# teclado_at_f340_smd_v2.net
KiCad netlist of a schematic drawn in EAGLE
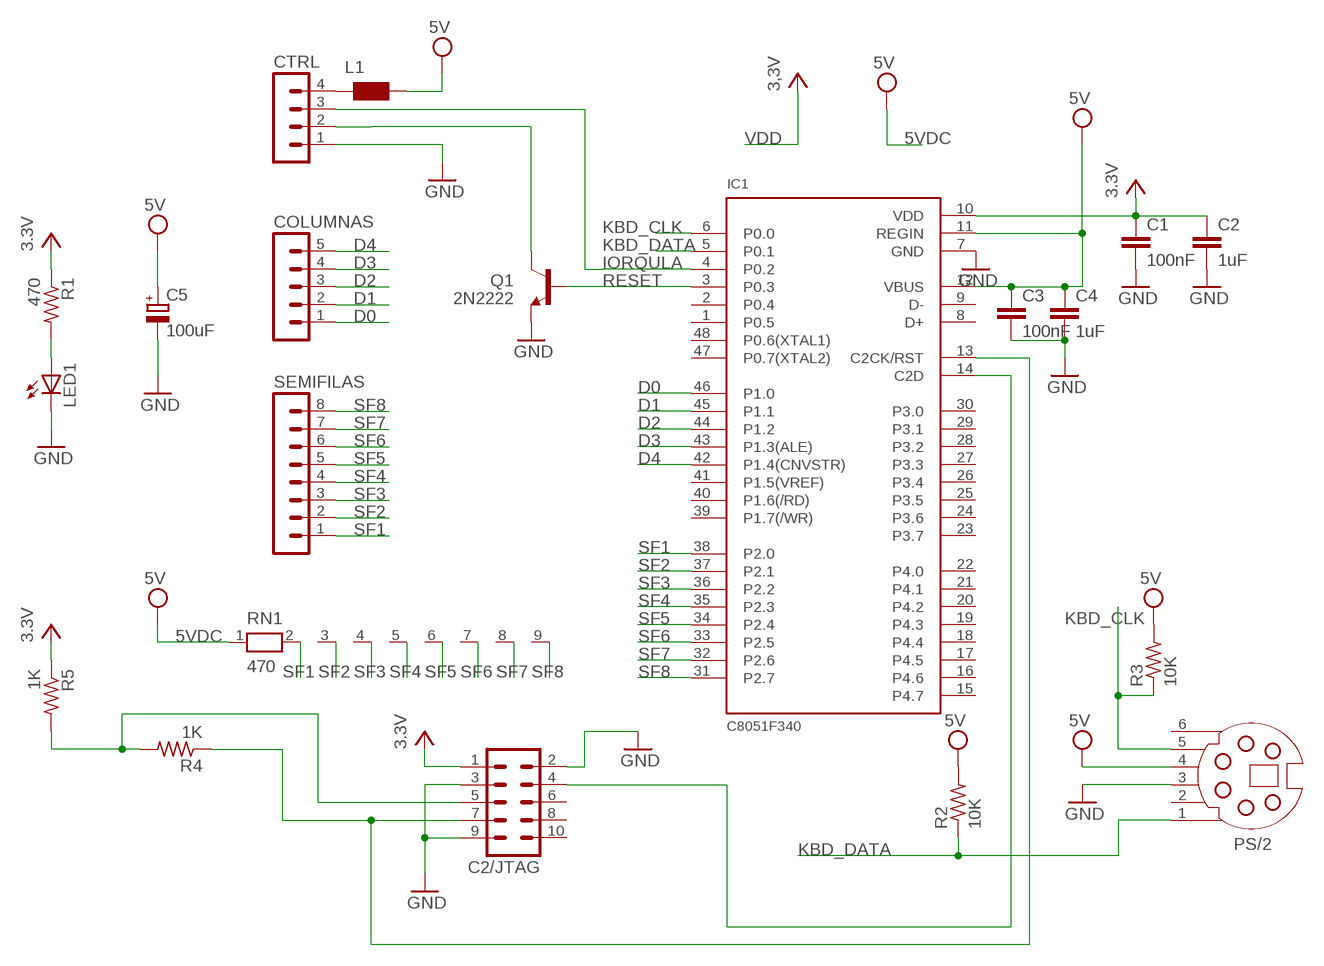
[diagram p0: schematic, sheet 1]

(export (version "E")
  (design (tool "Eeschema 10.0.6"))
  (components
    (comp (ref "C1")
      (value "100nF")
      (footprint "eagle-import:C0805K")
      (libsource (lib "eagle-import") (part "C-EUC0805K"))
    )
    (comp (ref "C2")
      (value "1uF")
      (footprint "eagle-import:C0805K")
      (libsource (lib "eagle-import") (part "C-EUC0805K"))
    )
    (comp (ref "C2/JTAG")
      (value "MA05-2")
      (footprint "eagle-import:MA05-2")
      (libsource (lib "eagle-import") (part "MA05-2"))
    )
    (comp (ref "C3")
      (value "100nF")
      (footprint "eagle-import:C0805K")
      (libsource (lib "eagle-import") (part "C-EUC0805K"))
    )
    (comp (ref "C4")
      (value "1uF")
      (footprint "eagle-import:C0805K")
      (libsource (lib "eagle-import") (part "C-EUC0805K"))
    )
    (comp (ref "C5")
      (value "100uF")
      (footprint "eagle-import:E2,5-6E")
      (libsource (lib "eagle-import") (part "CPOL-EUE2,5-6E"))
    )
    (comp (ref "COLUMNAS")
      (value "MA05-1")
      (footprint "eagle-import:MA05-1")
      (libsource (lib "eagle-import") (part "MA05-1"))
    )
    (comp (ref "CTRL")
      (value "MA04-1")
      (footprint "eagle-import:MA04-1")
      (libsource (lib "eagle-import") (part "MA04-1"))
    )
    (comp (ref "IC1")
      (value "C8051F340")
      (footprint "eagle-import:TQFP48")
      (libsource (lib "eagle-import") (part "C8051F340"))
    )
    (comp (ref "L1")
      (value "WE-CBF_0805")
      (footprint "eagle-import:0805")
      (libsource (lib "eagle-import") (part "WE-CBF_0805"))
    )
    (comp (ref "LED1")
      (value "LEDCHIP-LED0805")
      (footprint "eagle-import:CHIP-LED0805")
      (libsource (lib "eagle-import") (part "LEDCHIP-LED0805"))
    )
    (comp (ref "PS/2")
      (value "SSV-G06")
      (footprint "eagle-import:SSV-BC06")
      (libsource (lib "eagle-import") (part "SSV-G06"))
    )
    (comp (ref "Q1")
      (value "2N2222")
      (footprint "eagle-import:SOT23-3")
      (libsource (lib "eagle-import") (part "TRANSISTOR_NPNSOT23-3"))
    )
    (comp (ref "R1")
      (value "470")
      (footprint "eagle-import:M0805")
      (libsource (lib "eagle-import") (part "R-US_M0805"))
    )
    (comp (ref "R2")
      (value "10K")
      (footprint "eagle-import:M0805")
      (libsource (lib "eagle-import") (part "R-US_M0805"))
    )
    (comp (ref "R3")
      (value "10K")
      (footprint "eagle-import:M0805")
      (libsource (lib "eagle-import") (part "R-US_M0805"))
    )
    (comp (ref "R4")
      (value "1K")
      (footprint "eagle-import:M0805")
      (libsource (lib "eagle-import") (part "R-US_M0805"))
    )
    (comp (ref "R5")
      (value "1K")
      (footprint "eagle-import:M0805")
      (libsource (lib "eagle-import") (part "R-US_M0805"))
    )
    (comp (ref "RN1")
      (value "470")
      (footprint "eagle-import:RN-9")
      (libsource (lib "eagle-import") (part "RN08"))
    )
    (comp (ref "SEMIFILAS")
      (value "MA08-1")
      (footprint "eagle-import:MA08-1")
      (libsource (lib "eagle-import") (part "MA08-1"))
    )
  )
  (nets
    (net (code "1") (name "/D0") (class "Default")
      (node (ref "COLUMNAS") (pin "1") (pinfunction "1_1") (pintype "passive"))
      (node (ref "IC1") (pin "46") (pinfunction "P1.0_46") (pintype "bidirectional"))
    )
    (net (code "2") (name "/D1") (class "Default")
      (node (ref "COLUMNAS") (pin "2") (pinfunction "2_2") (pintype "passive"))
      (node (ref "IC1") (pin "45") (pinfunction "P1.1_45") (pintype "bidirectional"))
    )
    (net (code "3") (name "/D2") (class "Default")
      (node (ref "COLUMNAS") (pin "3") (pinfunction "3_3") (pintype "passive"))
      (node (ref "IC1") (pin "44") (pinfunction "P1.2_44") (pintype "bidirectional"))
    )
    (net (code "4") (name "/D3") (class "Default")
      (node (ref "COLUMNAS") (pin "4") (pinfunction "4_4") (pintype "passive"))
      (node (ref "IC1") (pin "43") (pinfunction "P1.3(ALE)_43") (pintype "bidirectional"))
    )
    (net (code "5") (name "/D4") (class "Default")
      (node (ref "COLUMNAS") (pin "5") (pinfunction "5_5") (pintype "passive"))
      (node (ref "IC1") (pin "42") (pinfunction "P1.4(CNVSTR)_42") (pintype "bidirectional"))
    )
    (net (code "6") (name "/IORQULA") (class "Default")
      (node (ref "CTRL") (pin "3") (pinfunction "3_3") (pintype "passive"))
      (node (ref "IC1") (pin "4") (pinfunction "P0.2_4") (pintype "bidirectional"))
    )
    (net (code "7") (name "/KBD_CLK") (class "Default")
      (node (ref "IC1") (pin "6") (pinfunction "P0.0_6") (pintype "bidirectional"))
      (node (ref "PS/2") (pin "5") (pinfunction "5_5") (pintype "passive"))
      (node (ref "R3") (pin "1") (pinfunction "1_1") (pintype "passive"))
    )
    (net (code "8") (name "/KBD_DATA") (class "Default")
      (node (ref "IC1") (pin "5") (pinfunction "P0.1_5") (pintype "bidirectional"))
      (node (ref "PS/2") (pin "1") (pinfunction "1_1") (pintype "passive"))
      (node (ref "R2") (pin "1") (pinfunction "1_1") (pintype "passive"))
    )
    (net (code "9") (name "/RESET") (class "Default")
      (node (ref "IC1") (pin "3") (pinfunction "P0.3_3") (pintype "bidirectional"))
      (node (ref "Q1") (pin "1") (pinfunction "B_1") (pintype "passive"))
    )
    (net (code "10") (name "/SF1") (class "Default")
      (node (ref "IC1") (pin "38") (pinfunction "P2.0_38") (pintype "bidirectional"))
      (node (ref "RN1") (pin "2") (pinfunction "2_2") (pintype "passive"))
      (node (ref "SEMIFILAS") (pin "1") (pinfunction "1_1") (pintype "passive"))
    )
    (net (code "11") (name "/SF2") (class "Default")
      (node (ref "IC1") (pin "37") (pinfunction "P2.1_37") (pintype "bidirectional"))
      (node (ref "RN1") (pin "3") (pinfunction "3_3") (pintype "passive"))
      (node (ref "SEMIFILAS") (pin "2") (pinfunction "2_2") (pintype "passive"))
    )
    (net (code "12") (name "/SF3") (class "Default")
      (node (ref "IC1") (pin "36") (pinfunction "P2.2_36") (pintype "bidirectional"))
      (node (ref "RN1") (pin "4") (pinfunction "4_4") (pintype "passive"))
      (node (ref "SEMIFILAS") (pin "3") (pinfunction "3_3") (pintype "passive"))
    )
    (net (code "13") (name "/SF4") (class "Default")
      (node (ref "IC1") (pin "35") (pinfunction "P2.3_35") (pintype "bidirectional"))
      (node (ref "RN1") (pin "5") (pinfunction "5_5") (pintype "passive"))
      (node (ref "SEMIFILAS") (pin "4") (pinfunction "4_4") (pintype "passive"))
    )
    (net (code "14") (name "/SF5") (class "Default")
      (node (ref "IC1") (pin "34") (pinfunction "P2.4_34") (pintype "bidirectional"))
      (node (ref "RN1") (pin "6") (pinfunction "6_6") (pintype "passive"))
      (node (ref "SEMIFILAS") (pin "5") (pinfunction "5_5") (pintype "passive"))
    )
    (net (code "15") (name "/SF6") (class "Default")
      (node (ref "IC1") (pin "33") (pinfunction "P2.5_33") (pintype "bidirectional"))
      (node (ref "RN1") (pin "7") (pinfunction "7_7") (pintype "passive"))
      (node (ref "SEMIFILAS") (pin "6") (pinfunction "6_6") (pintype "passive"))
    )
    (net (code "16") (name "/SF7") (class "Default")
      (node (ref "IC1") (pin "32") (pinfunction "P2.6_32") (pintype "bidirectional"))
      (node (ref "RN1") (pin "8") (pinfunction "8_8") (pintype "passive"))
      (node (ref "SEMIFILAS") (pin "7") (pinfunction "7_7") (pintype "passive"))
    )
    (net (code "17") (name "/SF8") (class "Default")
      (node (ref "IC1") (pin "31") (pinfunction "P2.7_31") (pintype "bidirectional"))
      (node (ref "RN1") (pin "9") (pinfunction "9_9") (pintype "passive"))
      (node (ref "SEMIFILAS") (pin "8") (pinfunction "8_8") (pintype "passive"))
    )
    (net (code "18") (name "3,3V") (class "Default")
      (node (ref "C1") (pin "1") (pinfunction "1_1") (pintype "passive"))
      (node (ref "C2") (pin "1") (pinfunction "1_1") (pintype "passive"))
      (node (ref "C2/JTAG") (pin "1") (pinfunction "1_1") (pintype "passive"))
      (node (ref "IC1") (pin "10") (pinfunction "VDD_10") (pintype "power_in"))
      (node (ref "R1") (pin "1") (pinfunction "1_1") (pintype "passive"))
      (node (ref "R5") (pin "1") (pinfunction "1_1") (pintype "passive"))
    )
    (net (code "19") (name "5V") (class "Default")
      (node (ref "C3") (pin "1") (pinfunction "1_1") (pintype "passive"))
      (node (ref "C4") (pin "1") (pinfunction "1_1") (pintype "passive"))
      (node (ref "C5") (pin "+") (pinfunction "+_+") (pintype "passive"))
      (node (ref "IC1") (pin "11") (pinfunction "REGIN_11") (pintype "power_in"))
      (node (ref "IC1") (pin "12") (pinfunction "VBUS_12") (pintype "power_in"))
      (node (ref "L1") (pin "2") (pinfunction "2_2") (pintype "passive"))
      (node (ref "PS/2") (pin "4") (pinfunction "4_4") (pintype "passive"))
      (node (ref "R2") (pin "2") (pinfunction "2_2") (pintype "passive"))
      (node (ref "R3") (pin "2") (pinfunction "2_2") (pintype "passive"))
      (node (ref "RN1") (pin "1") (pinfunction "1_1") (pintype "passive"))
    )
    (net (code "20") (name "GND") (class "Default")
      (node (ref "C1") (pin "2") (pinfunction "2_2") (pintype "passive"))
      (node (ref "C2") (pin "2") (pinfunction "2_2") (pintype "passive"))
      (node (ref "C2/JTAG") (pin "2") (pinfunction "2_2") (pintype "passive"))
      (node (ref "C2/JTAG") (pin "3") (pinfunction "3_3") (pintype "passive"))
      (node (ref "C2/JTAG") (pin "9") (pinfunction "9_9") (pintype "passive"))
      (node (ref "C3") (pin "2") (pinfunction "2_2") (pintype "passive"))
      (node (ref "C4") (pin "2") (pinfunction "2_2") (pintype "passive"))
      (node (ref "C5") (pin "-") (pinfunction "-_-") (pintype "passive"))
      (node (ref "CTRL") (pin "1") (pinfunction "1_1") (pintype "passive"))
      (node (ref "IC1") (pin "7") (pinfunction "GND_7") (pintype "power_in"))
      (node (ref "LED1") (pin "C") (pinfunction "C_C") (pintype "passive"))
      (node (ref "PS/2") (pin "3") (pinfunction "3_3") (pintype "passive"))
      (node (ref "Q1") (pin "2") (pinfunction "E_2") (pintype "passive"))
    )
    (net (code "21") (name "Net-(C2/JTAG-Pad5)") (class "Default")
      (node (ref "C2/JTAG") (pin "5") (pinfunction "5_5") (pintype "passive"))
      (node (ref "R4") (pin "2") (pinfunction "2_2") (pintype "passive"))
      (node (ref "R5") (pin "2") (pinfunction "2_2") (pintype "passive"))
    )
    (net (code "22") (name "Net-(CTRL-Pad4)") (class "Default")
      (node (ref "CTRL") (pin "4") (pinfunction "4_4") (pintype "passive"))
      (node (ref "L1") (pin "1") (pinfunction "1_1") (pintype "passive"))
    )
    (net (code "23") (name "Net-(IC1-C2CK{slash}RST)") (class "Default")
      (node (ref "C2/JTAG") (pin "7") (pinfunction "7_7") (pintype "passive"))
      (node (ref "IC1") (pin "13") (pinfunction "C2CK/RST_13") (pintype "bidirectional"))
      (node (ref "R4") (pin "1") (pinfunction "1_1") (pintype "passive"))
    )
    (net (code "24") (name "Net-(IC1-C2D)") (class "Default")
      (node (ref "C2/JTAG") (pin "4") (pinfunction "4_4") (pintype "passive"))
      (node (ref "IC1") (pin "14") (pinfunction "C2D_14") (pintype "bidirectional"))
    )
    (net (code "25") (name "Net-(LED1-PadA)") (class "Default")
      (node (ref "LED1") (pin "A") (pinfunction "A_A") (pintype "passive"))
      (node (ref "R1") (pin "2") (pinfunction "2_2") (pintype "passive"))
    )
    (net (code "26") (name "Net-(Q1-C)") (class "Default")
      (node (ref "CTRL") (pin "2") (pinfunction "2_2") (pintype "passive"))
      (node (ref "Q1") (pin "3") (pinfunction "C_3") (pintype "passive"))
    )
    (net (code "27") (name "unconnected-(C2/JTAG-Pad6)") (class "Default")
      (node (ref "C2/JTAG") (pin "6") (pinfunction "6_6") (pintype "passive"))
    )
    (net (code "28") (name "unconnected-(C2/JTAG-Pad8)") (class "Default")
      (node (ref "C2/JTAG") (pin "8") (pinfunction "8_8") (pintype "passive"))
    )
    (net (code "29") (name "unconnected-(C2/JTAG-Pad10)") (class "Default")
      (node (ref "C2/JTAG") (pin "10") (pinfunction "10_10") (pintype "passive"))
    )
    (net (code "30") (name "unconnected-(IC1-D+-Pad8)") (class "Default")
      (node (ref "IC1") (pin "8") (pinfunction "D+_8") (pintype "bidirectional"))
    )
    (net (code "31") (name "unconnected-(IC1-D--Pad9)") (class "Default")
      (node (ref "IC1") (pin "9") (pinfunction "D-_9") (pintype "bidirectional"))
    )
    (net (code "32") (name "unconnected-(IC1-P0.4-Pad2)") (class "Default")
      (node (ref "IC1") (pin "2") (pinfunction "P0.4_2") (pintype "bidirectional"))
    )
    (net (code "33") (name "unconnected-(IC1-P0.5-Pad1)") (class "Default")
      (node (ref "IC1") (pin "1") (pinfunction "P0.5_1") (pintype "bidirectional"))
    )
    (net (code "34") (name "unconnected-(IC1-P0.6(XTAL1)-Pad48)") (class "Default")
      (node (ref "IC1") (pin "48") (pinfunction "P0.6(XTAL1)_48") (pintype "bidirectional"))
    )
    (net (code "35") (name "unconnected-(IC1-P0.7(XTAL2)-Pad47)") (class "Default")
      (node (ref "IC1") (pin "47") (pinfunction "P0.7(XTAL2)_47") (pintype "bidirectional"))
    )
    (net (code "36") (name "unconnected-(IC1-P1.5(VREF)-Pad41)") (class "Default")
      (node (ref "IC1") (pin "41") (pinfunction "P1.5(VREF)_41") (pintype "bidirectional"))
    )
    (net (code "37") (name "unconnected-(IC1-P1.6({slash}RD)-Pad40)") (class "Default")
      (node (ref "IC1") (pin "40") (pinfunction "P1.6(/RD)_40") (pintype "bidirectional"))
    )
    (net (code "38") (name "unconnected-(IC1-P1.7({slash}WR)-Pad39)") (class "Default")
      (node (ref "IC1") (pin "39") (pinfunction "P1.7(/WR)_39") (pintype "bidirectional"))
    )
    (net (code "39") (name "unconnected-(IC1-P3.0-Pad30)") (class "Default")
      (node (ref "IC1") (pin "30") (pinfunction "P3.0_30") (pintype "bidirectional"))
    )
    (net (code "40") (name "unconnected-(IC1-P3.1-Pad29)") (class "Default")
      (node (ref "IC1") (pin "29") (pinfunction "P3.1_29") (pintype "bidirectional"))
    )
    (net (code "41") (name "unconnected-(IC1-P3.2-Pad28)") (class "Default")
      (node (ref "IC1") (pin "28") (pinfunction "P3.2_28") (pintype "bidirectional"))
    )
    (net (code "42") (name "unconnected-(IC1-P3.3-Pad27)") (class "Default")
      (node (ref "IC1") (pin "27") (pinfunction "P3.3_27") (pintype "bidirectional"))
    )
    (net (code "43") (name "unconnected-(IC1-P3.4-Pad26)") (class "Default")
      (node (ref "IC1") (pin "26") (pinfunction "P3.4_26") (pintype "bidirectional"))
    )
    (net (code "44") (name "unconnected-(IC1-P3.5-Pad25)") (class "Default")
      (node (ref "IC1") (pin "25") (pinfunction "P3.5_25") (pintype "bidirectional"))
    )
    (net (code "45") (name "unconnected-(IC1-P3.6-Pad24)") (class "Default")
      (node (ref "IC1") (pin "24") (pinfunction "P3.6_24") (pintype "bidirectional"))
    )
    (net (code "46") (name "unconnected-(IC1-P3.7-Pad23)") (class "Default")
      (node (ref "IC1") (pin "23") (pinfunction "P3.7_23") (pintype "bidirectional"))
    )
    (net (code "47") (name "unconnected-(IC1-P4.0-Pad22)") (class "Default")
      (node (ref "IC1") (pin "22") (pinfunction "P4.0_22") (pintype "bidirectional"))
    )
    (net (code "48") (name "unconnected-(IC1-P4.1-Pad21)") (class "Default")
      (node (ref "IC1") (pin "21") (pinfunction "P4.1_21") (pintype "bidirectional"))
    )
    (net (code "49") (name "unconnected-(IC1-P4.2-Pad20)") (class "Default")
      (node (ref "IC1") (pin "20") (pinfunction "P4.2_20") (pintype "bidirectional"))
    )
    (net (code "50") (name "unconnected-(IC1-P4.3-Pad19)") (class "Default")
      (node (ref "IC1") (pin "19") (pinfunction "P4.3_19") (pintype "bidirectional"))
    )
    (net (code "51") (name "unconnected-(IC1-P4.4-Pad18)") (class "Default")
      (node (ref "IC1") (pin "18") (pinfunction "P4.4_18") (pintype "bidirectional"))
    )
    (net (code "52") (name "unconnected-(IC1-P4.5-Pad17)") (class "Default")
      (node (ref "IC1") (pin "17") (pinfunction "P4.5_17") (pintype "bidirectional"))
    )
    (net (code "53") (name "unconnected-(IC1-P4.6-Pad16)") (class "Default")
      (node (ref "IC1") (pin "16") (pinfunction "P4.6_16") (pintype "bidirectional"))
    )
    (net (code "54") (name "unconnected-(IC1-P4.7-Pad15)") (class "Default")
      (node (ref "IC1") (pin "15") (pinfunction "P4.7_15") (pintype "bidirectional"))
    )
    (net (code "55") (name "unconnected-(PS/2-Pad2)") (class "Default")
      (node (ref "PS/2") (pin "2") (pinfunction "2_2") (pintype "passive"))
    )
    (net (code "56") (name "unconnected-(PS/2-Pad6)") (class "Default")
      (node (ref "PS/2") (pin "6") (pinfunction "6_6") (pintype "passive"))
    )
  )
)
